# 04_-_AUDIO.net
KiCad netlist of a schematic drawn in Altium Designer
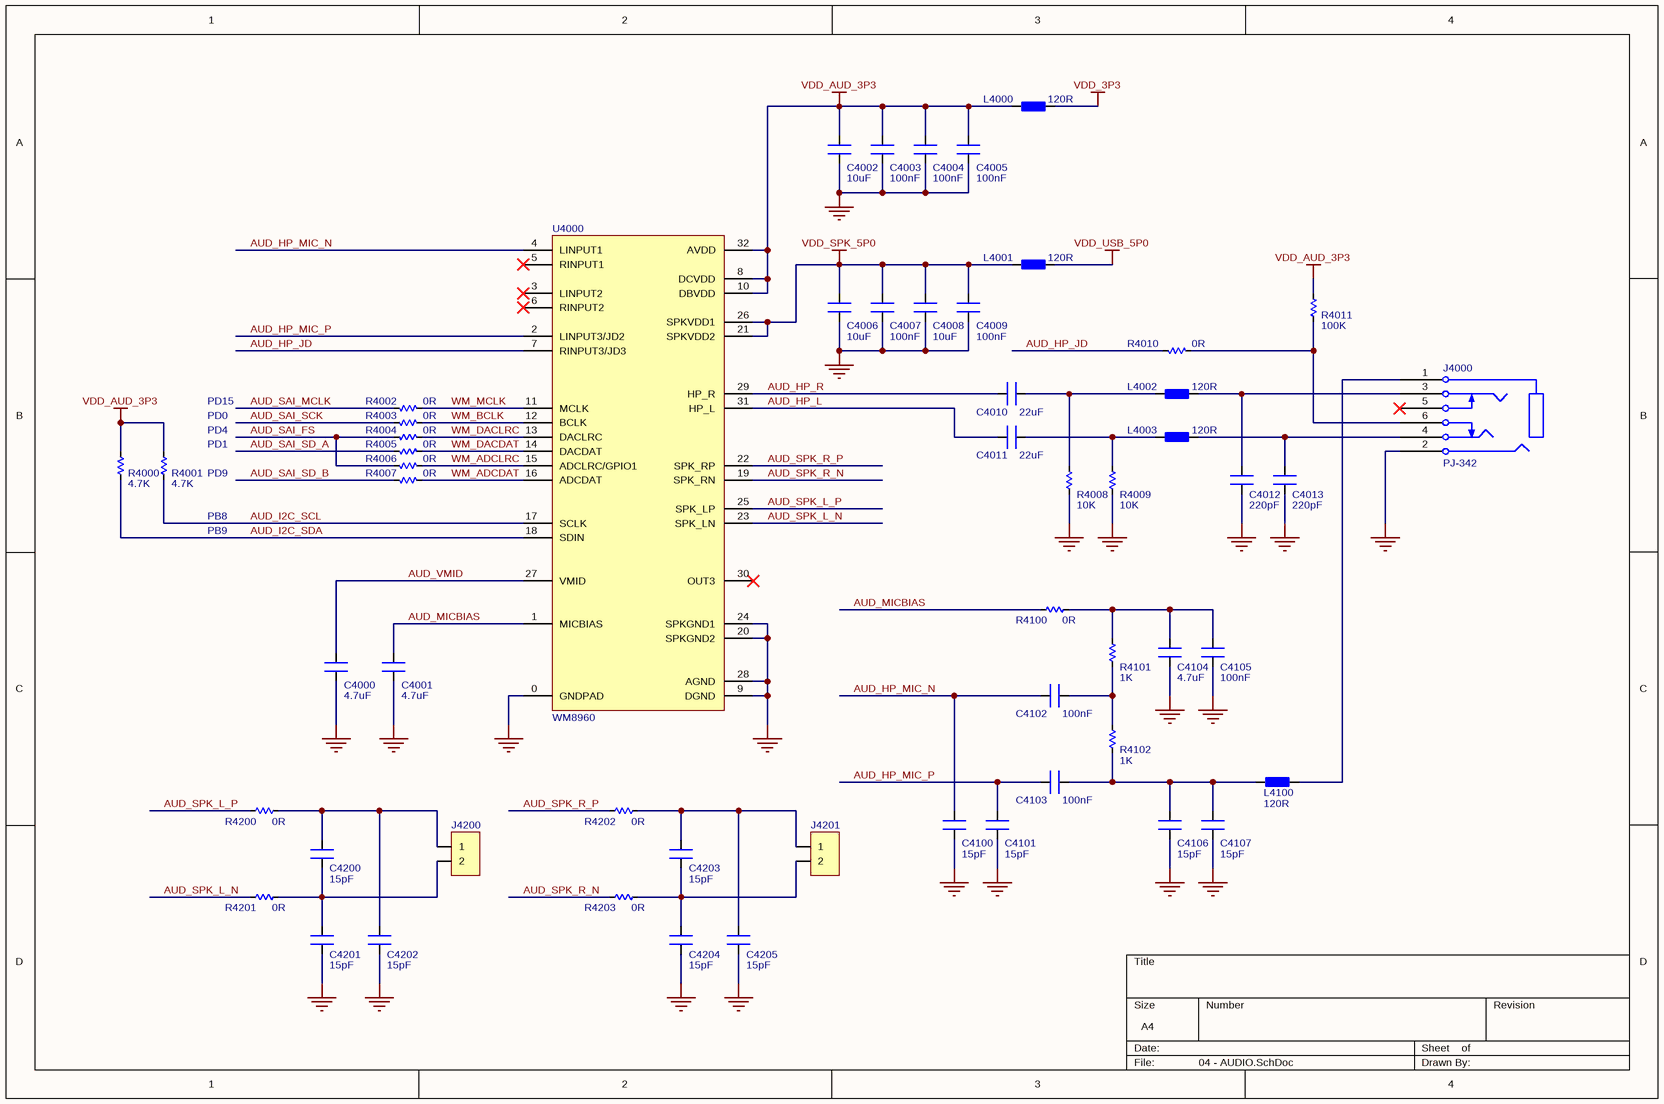
[diagram p0: 04 - AUDIO.SchDoc]

(export (version "E")
  (design (tool "Eeschema 10.0.6"))
  (components
    (comp (ref "C4000")
      (value "4.7uF")
      (footprint "CN-SMD-0402")
      (description "Ceramic Capacitor SMD 0402 4.7uF ±20% 10V")
      (fields (field (name "Comment") "Capacitor"))
      (libsource (lib "AS50") (part "Cap"))
    )
    (comp (ref "C4001")
      (value "4.7uF")
      (footprint "CN-SMD-0402")
      (description "Ceramic Capacitor SMD 0402 4.7uF ±20% 10V")
      (fields (field (name "Comment") "Capacitor"))
      (libsource (lib "AS50") (part "Cap"))
    )
    (comp (ref "C4002")
      (value "10uF")
      (footprint "CN-SMD-0603")
      (description "Ceramic Capacitor SMD 0603 10uF ±20% 10V")
      (fields (field (name "Comment") "Capacitor"))
      (libsource (lib "AS50") (part "Cap"))
    )
    (comp (ref "C4003")
      (value "100nF")
      (footprint "CN-SMD-0402")
      (description "Ceramic Capacitor SMD 0402 100nF ±20% 16V")
      (fields (field (name "Comment") "Capacitor"))
      (libsource (lib "AS50") (part "Cap"))
    )
    (comp (ref "C4004")
      (value "100nF")
      (footprint "CN-SMD-0402")
      (description "Ceramic Capacitor SMD 0402 100nF ±20% 16V")
      (fields (field (name "Comment") "Capacitor"))
      (libsource (lib "AS50") (part "Cap"))
    )
    (comp (ref "C4005")
      (value "100nF")
      (footprint "CN-SMD-0402")
      (description "Ceramic Capacitor SMD 0402 100nF ±20% 16V")
      (fields (field (name "Comment") "Capacitor"))
      (libsource (lib "AS50") (part "Cap"))
    )
    (comp (ref "C4006")
      (value "10uF")
      (footprint "CN-SMD-0603")
      (description "Ceramic Capacitor SMD 0603 10uF ±20% 10V")
      (fields (field (name "Comment") "Capacitor"))
      (libsource (lib "AS50") (part "Cap"))
    )
    (comp (ref "C4007")
      (value "100nF")
      (footprint "CN-SMD-0603")
      (description "Ceramic Capacitor SMD 0603 100nF ±20% 50V")
      (fields (field (name "Comment") "Capacitor"))
      (libsource (lib "AS50") (part "Cap"))
    )
    (comp (ref "C4008")
      (value "10uF")
      (footprint "CN-SMD-0603")
      (description "Ceramic Capacitor SMD 0603 10uF ±20% 10V")
      (fields (field (name "Comment") "Capacitor"))
      (libsource (lib "AS50") (part "Cap"))
    )
    (comp (ref "C4009")
      (value "100nF")
      (footprint "CN-SMD-0603")
      (description "Ceramic Capacitor SMD 0603 100nF ±20% 50V")
      (fields (field (name "Comment") "Capacitor"))
      (libsource (lib "AS50") (part "Cap"))
    )
    (comp (ref "C4010")
      (value "22uF")
      (footprint "CN-SMD-0603")
      (description "Ceramic Capacitor SMD 0603 22uF ±20% 6.3V")
      (fields (field (name "Comment") "Capacitor"))
      (libsource (lib "AS50") (part "Cap"))
    )
    (comp (ref "C4011")
      (value "22uF")
      (footprint "CN-SMD-0603")
      (description "Ceramic Capacitor SMD 0603 22uF ±20% 6.3V")
      (fields (field (name "Comment") "Capacitor"))
      (libsource (lib "AS50") (part "Cap"))
    )
    (comp (ref "C4012")
      (value "220pF")
      (footprint "CN-SMD-0402")
      (description "Ceramic Capacitor SMD 0402 220pF ±20% 50V")
      (fields (field (name "Comment") "Capacitor"))
      (libsource (lib "AS50") (part "Cap"))
    )
    (comp (ref "C4013")
      (value "220pF")
      (footprint "CN-SMD-0402")
      (description "Ceramic Capacitor SMD 0402 220pF ±20% 50V")
      (fields (field (name "Comment") "Capacitor"))
      (libsource (lib "AS50") (part "Cap"))
    )
    (comp (ref "C4100")
      (value "15pF")
      (footprint "CN-SMD-0402")
      (description "Ceramic Capacitor SMD 0402 15pF ±20% 50V")
      (fields (field (name "Comment") "Capacitor"))
      (libsource (lib "AS50") (part "Cap"))
    )
    (comp (ref "C4101")
      (value "15pF")
      (footprint "CN-SMD-0402")
      (description "Ceramic Capacitor SMD 0402 15pF ±20% 50V")
      (fields (field (name "Comment") "Capacitor"))
      (libsource (lib "AS50") (part "Cap"))
    )
    (comp (ref "C4102")
      (value "100nF")
      (footprint "CN-SMD-0402")
      (description "Ceramic Capacitor SMD 0402 100nF ±20% 16V")
      (fields (field (name "Comment") "Capacitor"))
      (libsource (lib "AS50") (part "Cap"))
    )
    (comp (ref "C4103")
      (value "100nF")
      (footprint "CN-SMD-0402")
      (description "Ceramic Capacitor SMD 0402 100nF ±20% 16V")
      (fields (field (name "Comment") "Capacitor"))
      (libsource (lib "AS50") (part "Cap"))
    )
    (comp (ref "C4104")
      (value "4.7uF")
      (footprint "CN-SMD-0402")
      (description "Ceramic Capacitor SMD 0402 4.7uF ±20% 10V")
      (fields (field (name "Comment") "Capacitor"))
      (libsource (lib "AS50") (part "Cap"))
    )
    (comp (ref "C4105")
      (value "100nF")
      (footprint "CN-SMD-0402")
      (description "Ceramic Capacitor SMD 0402 100nF ±20% 16V")
      (fields (field (name "Comment") "Capacitor"))
      (libsource (lib "AS50") (part "Cap"))
    )
    (comp (ref "C4106")
      (value "15pF")
      (footprint "CN-SMD-0402")
      (description "Ceramic Capacitor SMD 0402 15pF ±20% 50V")
      (fields (field (name "Comment") "Capacitor"))
      (libsource (lib "AS50") (part "Cap"))
    )
    (comp (ref "C4107")
      (value "15pF")
      (footprint "CN-SMD-0402")
      (description "Ceramic Capacitor SMD 0402 15pF ±20% 50V")
      (fields (field (name "Comment") "Capacitor"))
      (libsource (lib "AS50") (part "Cap"))
    )
    (comp (ref "C4200")
      (value "15pF")
      (footprint "CN-SMD-0402")
      (description "Ceramic Capacitor SMD 0402 15pF ±20% 50V")
      (fields (field (name "Comment") "Capacitor"))
      (libsource (lib "AS50") (part "Cap"))
    )
    (comp (ref "C4201")
      (value "15pF")
      (footprint "CN-SMD-0402")
      (description "Ceramic Capacitor SMD 0402 15pF ±20% 50V")
      (fields (field (name "Comment") "Capacitor"))
      (libsource (lib "AS50") (part "Cap"))
    )
    (comp (ref "C4202")
      (value "15pF")
      (footprint "CN-SMD-0402")
      (description "Ceramic Capacitor SMD 0402 15pF ±20% 50V")
      (fields (field (name "Comment") "Capacitor"))
      (libsource (lib "AS50") (part "Cap"))
    )
    (comp (ref "C4203")
      (value "15pF")
      (footprint "CN-SMD-0402")
      (description "Ceramic Capacitor SMD 0402 15pF ±20% 50V")
      (fields (field (name "Comment") "Capacitor"))
      (libsource (lib "AS50") (part "Cap"))
    )
    (comp (ref "C4204")
      (value "15pF")
      (footprint "CN-SMD-0402")
      (description "Ceramic Capacitor SMD 0402 15pF ±20% 50V")
      (fields (field (name "Comment") "Capacitor"))
      (libsource (lib "AS50") (part "Cap"))
    )
    (comp (ref "C4205")
      (value "15pF")
      (footprint "CN-SMD-0402")
      (description "Ceramic Capacitor SMD 0402 15pF ±20% 50V")
      (fields (field (name "Comment") "Capacitor"))
      (libsource (lib "AS50") (part "Cap"))
    )
    (comp (ref "J4000")
      (value "PJ-342")
      (footprint "AUDIO_PJ-342")
      (description "Audio connector PJ-342 3.5mm 4-pole")
      (libsource (lib "AS50") (part "PJ-342"))
    )
    (comp (ref "J4200")
      (value "JP2")
      (footprint "JP2-D1T")
      (description "Single 2-pin jumper")
      (libsource (lib "AS50") (part "JP2"))
    )
    (comp (ref "J4201")
      (value "JP2")
      (footprint "JP2-D1T")
      (description "Single 2-pin jumper")
      (libsource (lib "AS50") (part "JP2"))
    )
    (comp (ref "L4000")
      (value "120R")
      (footprint "L-SMD-0402")
      (description "Ferrite bead SMD 0402 120 Ohm @100MHz")
      (fields (field (name "Comment") "Ferrite bead"))
      (libsource (lib "AS50") (part "Ferrite bead"))
    )
    (comp (ref "L4001")
      (value "120R")
      (footprint "L-SMD-0603")
      (description "Ferrite bead SMD 0603 120 Ohm @100MHz")
      (fields (field (name "Comment") "Ferrite bead"))
      (libsource (lib "AS50") (part "Ferrite bead"))
    )
    (comp (ref "L4002")
      (value "120R")
      (footprint "L-SMD-0402")
      (description "Ferrite bead SMD 0402 120 Ohm @100MHz")
      (fields (field (name "Comment") "Ferrite bead"))
      (libsource (lib "AS50") (part "Ferrite bead"))
    )
    (comp (ref "L4003")
      (value "120R")
      (footprint "L-SMD-0402")
      (description "Ferrite bead SMD 0402 120 Ohm @100MHz")
      (fields (field (name "Comment") "Ferrite bead"))
      (libsource (lib "AS50") (part "Ferrite bead"))
    )
    (comp (ref "L4100")
      (value "120R")
      (footprint "L-SMD-0402")
      (description "Ferrite bead SMD 0402 120 Ohm @100MHz")
      (fields (field (name "Comment") "Ferrite bead"))
      (libsource (lib "AS50") (part "Ferrite bead"))
    )
    (comp (ref "R4000")
      (value "4.7K")
      (footprint "RES-SMD-0402")
      (description "Resistor SMD 0402 4.7K 1% 0.063W")
      (fields (field (name "Comment") "Resistor"))
      (libsource (lib "AS50") (part "Res"))
    )
    (comp (ref "R4001")
      (value "4.7K")
      (footprint "RES-SMD-0402")
      (description "Resistor SMD 0402 4.7K 1% 0.063W")
      (fields (field (name "Comment") "Resistor"))
      (libsource (lib "AS50") (part "Res"))
    )
    (comp (ref "R4002")
      (value "0R")
      (footprint "RES-SMD-0402")
      (description "Resistor SMD 0402 0R 1% 0.063W")
      (fields (field (name "Comment") "Resistor"))
      (libsource (lib "AS50") (part "Res"))
    )
    (comp (ref "R4003")
      (value "0R")
      (footprint "RES-SMD-0402")
      (description "Resistor SMD 0402 0R 1% 0.063W")
      (fields (field (name "Comment") "Resistor"))
      (libsource (lib "AS50") (part "Res"))
    )
    (comp (ref "R4004")
      (value "0R")
      (footprint "RES-SMD-0402")
      (description "Resistor SMD 0402 0R 1% 0.063W")
      (fields (field (name "Comment") "Resistor"))
      (libsource (lib "AS50") (part "Res"))
    )
    (comp (ref "R4005")
      (value "0R")
      (footprint "RES-SMD-0402")
      (description "Resistor SMD 0402 0R 1% 0.063W")
      (fields (field (name "Comment") "Resistor"))
      (libsource (lib "AS50") (part "Res"))
    )
    (comp (ref "R4006")
      (value "0R")
      (footprint "RES-SMD-0402")
      (description "Resistor SMD 0402 0R 1% 0.063W")
      (fields (field (name "Comment") "Resistor"))
      (libsource (lib "AS50") (part "Res"))
    )
    (comp (ref "R4007")
      (value "0R")
      (footprint "RES-SMD-0402")
      (description "Resistor SMD 0402 0R 1% 0.063W")
      (fields (field (name "Comment") "Resistor"))
      (libsource (lib "AS50") (part "Res"))
    )
    (comp (ref "R4008")
      (value "10K")
      (footprint "RES-SMD-0402")
      (description "Resistor SMD 0402 10K 1% 0.063W")
      (fields (field (name "Comment") "Resistor"))
      (libsource (lib "AS50") (part "Res"))
    )
    (comp (ref "R4009")
      (value "10K")
      (footprint "RES-SMD-0402")
      (description "Resistor SMD 0402 10K 1% 0.063W")
      (fields (field (name "Comment") "Resistor"))
      (libsource (lib "AS50") (part "Res"))
    )
    (comp (ref "R4010")
      (value "0R")
      (footprint "RES-SMD-0402")
      (description "Resistor SMD 0402 0R 1% 0.063W")
      (fields (field (name "Comment") "Resistor"))
      (libsource (lib "AS50") (part "Res"))
    )
    (comp (ref "R4011")
      (value "100K")
      (footprint "RES-SMD-0402")
      (description "Resistor SMD 0402 100K 1% 0.063W")
      (fields (field (name "Comment") "Resistor"))
      (libsource (lib "AS50") (part "Res"))
    )
    (comp (ref "R4100")
      (value "0R")
      (footprint "RES-SMD-0402")
      (description "Resistor SMD 0402 0R 1% 0.063W")
      (fields (field (name "Comment") "Resistor"))
      (libsource (lib "AS50") (part "Res"))
    )
    (comp (ref "R4101")
      (value "1K")
      (footprint "RES-SMD-0402")
      (description "Resistor SMD 0402 1K 1% 0.063W")
      (fields (field (name "Comment") "Resistor"))
      (libsource (lib "AS50") (part "Res"))
    )
    (comp (ref "R4102")
      (value "1K")
      (footprint "RES-SMD-0402")
      (description "Resistor SMD 0402 1K 1% 0.063W")
      (fields (field (name "Comment") "Resistor"))
      (libsource (lib "AS50") (part "Res"))
    )
    (comp (ref "R4200")
      (value "0R")
      (footprint "RES-SMD-0402")
      (description "Resistor SMD 0402 0R 1% 0.063W")
      (fields (field (name "Comment") "Resistor"))
      (libsource (lib "AS50") (part "Res"))
    )
    (comp (ref "R4201")
      (value "0R")
      (footprint "RES-SMD-0402")
      (description "Resistor SMD 0402 0R 1% 0.063W")
      (fields (field (name "Comment") "Resistor"))
      (libsource (lib "AS50") (part "Res"))
    )
    (comp (ref "R4202")
      (value "0R")
      (footprint "RES-SMD-0402")
      (description "Resistor SMD 0402 0R 1% 0.063W")
      (fields (field (name "Comment") "Resistor"))
      (libsource (lib "AS50") (part "Res"))
    )
    (comp (ref "R4203")
      (value "0R")
      (footprint "RES-SMD-0402")
      (description "Resistor SMD 0402 0R 1% 0.063W")
      (fields (field (name "Comment") "Resistor"))
      (libsource (lib "AS50") (part "Res"))
    )
    (comp (ref "U4000")
      (value "WM8960")
      (footprint "QFN50P500X500X100-33N-D")
      (libsource (lib "AS50") (part "WM8960"))
    )
  )
  (nets
    (net (code "1") (name "/AUD_HP_JD") (class "Default")
      (node (ref "R4010") (pin "2") (pinfunction "2_2") (pintype "passive"))
      (node (ref "U4000") (pin "7") (pinfunction "RINPUT3/JD3_7") (pintype "passive"))
    )
    (net (code "2") (name "/AUD_HP_L") (class "Default")
      (node (ref "C4011") (pin "2") (pinfunction "2_2") (pintype "passive"))
      (node (ref "U4000") (pin "31") (pinfunction "HP_L_31") (pintype "passive"))
    )
    (net (code "3") (name "/AUD_HP_MIC_N") (class "Default")
      (node (ref "C4100") (pin "2") (pinfunction "2_2") (pintype "passive"))
      (node (ref "C4102") (pin "2") (pinfunction "2_2") (pintype "passive"))
      (node (ref "U4000") (pin "4") (pinfunction "LINPUT1_4") (pintype "passive"))
    )
    (net (code "4") (name "/AUD_HP_MIC_P") (class "Default")
      (node (ref "C4101") (pin "2") (pinfunction "2_2") (pintype "passive"))
      (node (ref "C4103") (pin "2") (pinfunction "2_2") (pintype "passive"))
      (node (ref "U4000") (pin "2") (pinfunction "LINPUT3/JD2_2") (pintype "passive"))
    )
    (net (code "5") (name "/AUD_HP_R") (class "Default")
      (node (ref "C4010") (pin "2") (pinfunction "2_2") (pintype "passive"))
      (node (ref "U4000") (pin "29") (pinfunction "HP_R_29") (pintype "passive"))
    )
    (net (code "6") (name "/AUD_I2C_SCL") (class "Default")
      (node (ref "R4001") (pin "2") (pinfunction "2_2") (pintype "passive"))
      (node (ref "U4000") (pin "17") (pinfunction "SCLK_17") (pintype "passive"))
    )
    (net (code "7") (name "/AUD_I2C_SDA") (class "Default")
      (node (ref "R4000") (pin "2") (pinfunction "2_2") (pintype "passive"))
      (node (ref "U4000") (pin "18") (pinfunction "SDIN_18") (pintype "passive"))
    )
    (net (code "8") (name "/AUD_MICBIAS") (class "Default")
      (node (ref "C4001") (pin "2") (pinfunction "2_2") (pintype "passive"))
      (node (ref "R4100") (pin "1") (pinfunction "1_1") (pintype "passive"))
      (node (ref "U4000") (pin "1") (pinfunction "MICBIAS_1") (pintype "passive"))
    )
    (net (code "9") (name "/AUD_SAI_FS") (class "Default")
      (node (ref "R4004") (pin "2") (pinfunction "2_2") (pintype "passive"))
      (node (ref "R4006") (pin "2") (pinfunction "2_2") (pintype "passive"))
    )
    (net (code "10") (name "/AUD_SAI_MCLK") (class "Default")
      (node (ref "R4002") (pin "2") (pinfunction "2_2") (pintype "passive"))
    )
    (net (code "11") (name "/AUD_SAI_SCK") (class "Default")
      (node (ref "R4003") (pin "2") (pinfunction "2_2") (pintype "passive"))
    )
    (net (code "12") (name "/AUD_SAI_SD_A") (class "Default")
      (node (ref "R4005") (pin "2") (pinfunction "2_2") (pintype "passive"))
    )
    (net (code "13") (name "/AUD_SAI_SD_B") (class "Default")
      (node (ref "R4007") (pin "2") (pinfunction "2_2") (pintype "passive"))
    )
    (net (code "14") (name "/AUD_SPK_L_N") (class "Default")
      (node (ref "R4201") (pin "1") (pinfunction "1_1") (pintype "passive"))
      (node (ref "U4000") (pin "23") (pinfunction "SPK_LN_23") (pintype "passive"))
    )
    (net (code "15") (name "/AUD_SPK_L_P") (class "Default")
      (node (ref "R4200") (pin "1") (pinfunction "1_1") (pintype "passive"))
      (node (ref "U4000") (pin "25") (pinfunction "SPK_LP_25") (pintype "passive"))
    )
    (net (code "16") (name "/AUD_SPK_R_N") (class "Default")
      (node (ref "R4203") (pin "1") (pinfunction "1_1") (pintype "passive"))
      (node (ref "U4000") (pin "19") (pinfunction "SPK_RN_19") (pintype "passive"))
    )
    (net (code "17") (name "/AUD_SPK_R_P") (class "Default")
      (node (ref "R4202") (pin "1") (pinfunction "1_1") (pintype "passive"))
      (node (ref "U4000") (pin "22") (pinfunction "SPK_RP_22") (pintype "passive"))
    )
    (net (code "18") (name "/AUD_VMID") (class "Default")
      (node (ref "C4000") (pin "2") (pinfunction "2_2") (pintype "passive"))
      (node (ref "U4000") (pin "27") (pinfunction "VMID_27") (pintype "passive"))
    )
    (net (code "19") (name "/WM_ADCDAT") (class "Default")
      (node (ref "R4007") (pin "1") (pinfunction "1_1") (pintype "passive"))
      (node (ref "U4000") (pin "16") (pinfunction "ADCDAT_16") (pintype "passive"))
    )
    (net (code "20") (name "/WM_ADCLRC") (class "Default")
      (node (ref "R4006") (pin "1") (pinfunction "1_1") (pintype "passive"))
      (node (ref "U4000") (pin "15") (pinfunction "ADCLRC/GPIO1_15") (pintype "passive"))
    )
    (net (code "21") (name "/WM_BCLK") (class "Default")
      (node (ref "R4003") (pin "1") (pinfunction "1_1") (pintype "passive"))
      (node (ref "U4000") (pin "12") (pinfunction "BCLK_12") (pintype "passive"))
    )
    (net (code "22") (name "/WM_DACDAT") (class "Default")
      (node (ref "R4005") (pin "1") (pinfunction "1_1") (pintype "passive"))
      (node (ref "U4000") (pin "14") (pinfunction "DACDAT_14") (pintype "passive"))
    )
    (net (code "23") (name "/WM_DACLRC") (class "Default")
      (node (ref "R4004") (pin "1") (pinfunction "1_1") (pintype "passive"))
      (node (ref "U4000") (pin "13") (pinfunction "DACLRC_13") (pintype "passive"))
    )
    (net (code "24") (name "/WM_MCLK") (class "Default")
      (node (ref "R4002") (pin "1") (pinfunction "1_1") (pintype "passive"))
      (node (ref "U4000") (pin "11") (pinfunction "MCLK_11") (pintype "passive"))
    )
    (net (code "25") (name "GND") (class "Default")
      (node (ref "C4000") (pin "1") (pinfunction "1_1") (pintype "passive"))
      (node (ref "C4001") (pin "1") (pinfunction "1_1") (pintype "passive"))
      (node (ref "C4002") (pin "1") (pinfunction "1_1") (pintype "passive"))
      (node (ref "C4003") (pin "1") (pinfunction "1_1") (pintype "passive"))
      (node (ref "C4004") (pin "1") (pinfunction "1_1") (pintype "passive"))
      (node (ref "C4005") (pin "1") (pinfunction "1_1") (pintype "passive"))
      (node (ref "C4006") (pin "1") (pinfunction "1_1") (pintype "passive"))
      (node (ref "C4007") (pin "1") (pinfunction "1_1") (pintype "passive"))
      (node (ref "C4008") (pin "1") (pinfunction "1_1") (pintype "passive"))
      (node (ref "C4009") (pin "1") (pinfunction "1_1") (pintype "passive"))
      (node (ref "C4012") (pin "1") (pinfunction "1_1") (pintype "passive"))
      (node (ref "C4013") (pin "1") (pinfunction "1_1") (pintype "passive"))
      (node (ref "C4100") (pin "1") (pinfunction "1_1") (pintype "passive"))
      (node (ref "C4101") (pin "1") (pinfunction "1_1") (pintype "passive"))
      (node (ref "C4104") (pin "1") (pinfunction "1_1") (pintype "passive"))
      (node (ref "C4105") (pin "1") (pinfunction "1_1") (pintype "passive"))
      (node (ref "C4106") (pin "1") (pinfunction "1_1") (pintype "passive"))
      (node (ref "C4107") (pin "1") (pinfunction "1_1") (pintype "passive"))
      (node (ref "C4201") (pin "1") (pinfunction "1_1") (pintype "passive"))
      (node (ref "C4202") (pin "1") (pinfunction "1_1") (pintype "passive"))
      (node (ref "C4204") (pin "1") (pinfunction "1_1") (pintype "passive"))
      (node (ref "C4205") (pin "1") (pinfunction "1_1") (pintype "passive"))
      (node (ref "J4000") (pin "2") (pinfunction "GND_2") (pintype "passive"))
      (node (ref "R4008") (pin "2") (pinfunction "2_2") (pintype "passive"))
      (node (ref "R4009") (pin "2") (pinfunction "2_2") (pintype "passive"))
      (node (ref "U4000") (pin "0") (pinfunction "GNDPAD_0") (pintype "passive"))
      (node (ref "U4000") (pin "20") (pinfunction "SPKGND2_20") (pintype "passive"))
      (node (ref "U4000") (pin "24") (pinfunction "SPKGND1_24") (pintype "passive"))
      (node (ref "U4000") (pin "28") (pinfunction "AGND_28") (pintype "passive"))
      (node (ref "U4000") (pin "9") (pinfunction "DGND_9") (pintype "passive"))
    )
    (net (code "26") (name "Net-(C4010-Pad1)") (class "Default")
      (node (ref "C4010") (pin "1") (pinfunction "1_1") (pintype "passive"))
      (node (ref "L4002") (pin "2") (pinfunction "2_2") (pintype "passive"))
      (node (ref "R4008") (pin "1") (pinfunction "1_1") (pintype "passive"))
    )
    (net (code "27") (name "Net-(C4011-Pad1)") (class "Default")
      (node (ref "C4011") (pin "1") (pinfunction "1_1") (pintype "passive"))
      (node (ref "L4003") (pin "2") (pinfunction "2_2") (pintype "passive"))
      (node (ref "R4009") (pin "1") (pinfunction "1_1") (pintype "passive"))
    )
    (net (code "28") (name "Net-(C4102-Pad1)") (class "Default")
      (node (ref "C4102") (pin "1") (pinfunction "1_1") (pintype "passive"))
      (node (ref "R4101") (pin "2") (pinfunction "2_2") (pintype "passive"))
      (node (ref "R4102") (pin "1") (pinfunction "1_1") (pintype "passive"))
    )
    (net (code "29") (name "Net-(C4103-Pad1)") (class "Default")
      (node (ref "C4103") (pin "1") (pinfunction "1_1") (pintype "passive"))
      (node (ref "C4106") (pin "2") (pinfunction "2_2") (pintype "passive"))
      (node (ref "C4107") (pin "2") (pinfunction "2_2") (pintype "passive"))
      (node (ref "L4100") (pin "2") (pinfunction "2_2") (pintype "passive"))
      (node (ref "R4102") (pin "2") (pinfunction "2_2") (pintype "passive"))
    )
    (net (code "30") (name "Net-(C4104-Pad2)") (class "Default")
      (node (ref "C4104") (pin "2") (pinfunction "2_2") (pintype "passive"))
      (node (ref "C4105") (pin "2") (pinfunction "2_2") (pintype "passive"))
      (node (ref "R4100") (pin "2") (pinfunction "2_2") (pintype "passive"))
      (node (ref "R4101") (pin "1") (pinfunction "1_1") (pintype "passive"))
    )
    (net (code "31") (name "Net-(C4200-Pad1)") (class "Default")
      (node (ref "C4200") (pin "1") (pinfunction "1_1") (pintype "passive"))
      (node (ref "C4201") (pin "2") (pinfunction "2_2") (pintype "passive"))
      (node (ref "J4200") (pin "2") (pinfunction "2_2") (pintype "passive"))
      (node (ref "R4201") (pin "2") (pinfunction "2_2") (pintype "passive"))
    )
    (net (code "32") (name "Net-(C4200-Pad2)") (class "Default")
      (node (ref "C4200") (pin "2") (pinfunction "2_2") (pintype "passive"))
      (node (ref "C4202") (pin "2") (pinfunction "2_2") (pintype "passive"))
      (node (ref "J4200") (pin "1") (pinfunction "1_1") (pintype "passive"))
      (node (ref "R4200") (pin "2") (pinfunction "2_2") (pintype "passive"))
    )
    (net (code "33") (name "Net-(C4203-Pad1)") (class "Default")
      (node (ref "C4203") (pin "1") (pinfunction "1_1") (pintype "passive"))
      (node (ref "C4204") (pin "2") (pinfunction "2_2") (pintype "passive"))
      (node (ref "J4201") (pin "2") (pinfunction "2_2") (pintype "passive"))
      (node (ref "R4203") (pin "2") (pinfunction "2_2") (pintype "passive"))
    )
    (net (code "34") (name "Net-(C4203-Pad2)") (class "Default")
      (node (ref "C4203") (pin "2") (pinfunction "2_2") (pintype "passive"))
      (node (ref "C4205") (pin "2") (pinfunction "2_2") (pintype "passive"))
      (node (ref "J4201") (pin "1") (pinfunction "1_1") (pintype "passive"))
      (node (ref "R4202") (pin "2") (pinfunction "2_2") (pintype "passive"))
    )
    (net (code "35") (name "Net-(J4000-LEFT)") (class "Default")
      (node (ref "C4013") (pin "2") (pinfunction "2_2") (pintype "passive"))
      (node (ref "J4000") (pin "4") (pinfunction "LEFT_4") (pintype "passive"))
      (node (ref "L4003") (pin "1") (pinfunction "1_1") (pintype "passive"))
    )
    (net (code "36") (name "Net-(J4000-MIC)") (class "Default")
      (node (ref "J4000") (pin "1") (pinfunction "MIC_1") (pintype "passive"))
      (node (ref "L4100") (pin "1") (pinfunction "1_1") (pintype "passive"))
    )
    (net (code "37") (name "Net-(J4000-Pad6)") (class "Default")
      (node (ref "J4000") (pin "6") (pintype "passive"))
      (node (ref "R4010") (pin "1") (pinfunction "1_1") (pintype "passive"))
      (node (ref "R4011") (pin "2") (pinfunction "2_2") (pintype "passive"))
    )
    (net (code "38") (name "Net-(J4000-RIGHT)") (class "Default")
      (node (ref "C4012") (pin "2") (pinfunction "2_2") (pintype "passive"))
      (node (ref "J4000") (pin "3") (pinfunction "RIGHT_3") (pintype "passive"))
      (node (ref "L4002") (pin "1") (pinfunction "1_1") (pintype "passive"))
    )
    (net (code "39") (name "VDD_3P3") (class "Default")
      (node (ref "L4000") (pin "1") (pinfunction "1_1") (pintype "passive"))
    )
    (net (code "40") (name "VDD_AUD_3P3") (class "Default")
      (node (ref "C4002") (pin "2") (pinfunction "2_2") (pintype "passive"))
      (node (ref "C4003") (pin "2") (pinfunction "2_2") (pintype "passive"))
      (node (ref "C4004") (pin "2") (pinfunction "2_2") (pintype "passive"))
      (node (ref "C4005") (pin "2") (pinfunction "2_2") (pintype "passive"))
      (node (ref "L4000") (pin "2") (pinfunction "2_2") (pintype "passive"))
      (node (ref "R4000") (pin "1") (pinfunction "1_1") (pintype "passive"))
      (node (ref "R4001") (pin "1") (pinfunction "1_1") (pintype "passive"))
      (node (ref "R4011") (pin "1") (pinfunction "1_1") (pintype "passive"))
      (node (ref "U4000") (pin "10") (pinfunction "DBVDD_10") (pintype "passive"))
      (node (ref "U4000") (pin "32") (pinfunction "AVDD_32") (pintype "passive"))
      (node (ref "U4000") (pin "8") (pinfunction "DCVDD_8") (pintype "passive"))
    )
    (net (code "41") (name "VDD_SPK_5P0") (class "Default")
      (node (ref "C4006") (pin "2") (pinfunction "2_2") (pintype "passive"))
      (node (ref "C4007") (pin "2") (pinfunction "2_2") (pintype "passive"))
      (node (ref "C4008") (pin "2") (pinfunction "2_2") (pintype "passive"))
      (node (ref "C4009") (pin "2") (pinfunction "2_2") (pintype "passive"))
      (node (ref "L4001") (pin "2") (pinfunction "2_2") (pintype "passive"))
      (node (ref "U4000") (pin "21") (pinfunction "SPKVDD2_21") (pintype "passive"))
      (node (ref "U4000") (pin "26") (pinfunction "SPKVDD1_26") (pintype "passive"))
    )
    (net (code "42") (name "VDD_USB_5P0") (class "Default")
      (node (ref "L4001") (pin "1") (pinfunction "1_1") (pintype "passive"))
    )
    (net (code "43") (name "unconnected-(J4000-Pad5)") (class "Default")
      (node (ref "J4000") (pin "5") (pintype "passive+no_connect"))
    )
    (net (code "44") (name "unconnected-(U4000-LINPUT2-Pad3)") (class "Default")
      (node (ref "U4000") (pin "3") (pinfunction "LINPUT2_3") (pintype "passive+no_connect"))
    )
    (net (code "45") (name "unconnected-(U4000-OUT3-Pad30)") (class "Default")
      (node (ref "U4000") (pin "30") (pinfunction "OUT3_30") (pintype "passive+no_connect"))
    )
    (net (code "46") (name "unconnected-(U4000-RINPUT1-Pad5)") (class "Default")
      (node (ref "U4000") (pin "5") (pinfunction "RINPUT1_5") (pintype "passive+no_connect"))
    )
    (net (code "47") (name "unconnected-(U4000-RINPUT2-Pad6)") (class "Default")
      (node (ref "U4000") (pin "6") (pinfunction "RINPUT2_6") (pintype "passive+no_connect"))
    )
  )
)
